# FG_Sce.net
KiCad netlist of a schematic drawn in Altium Designer
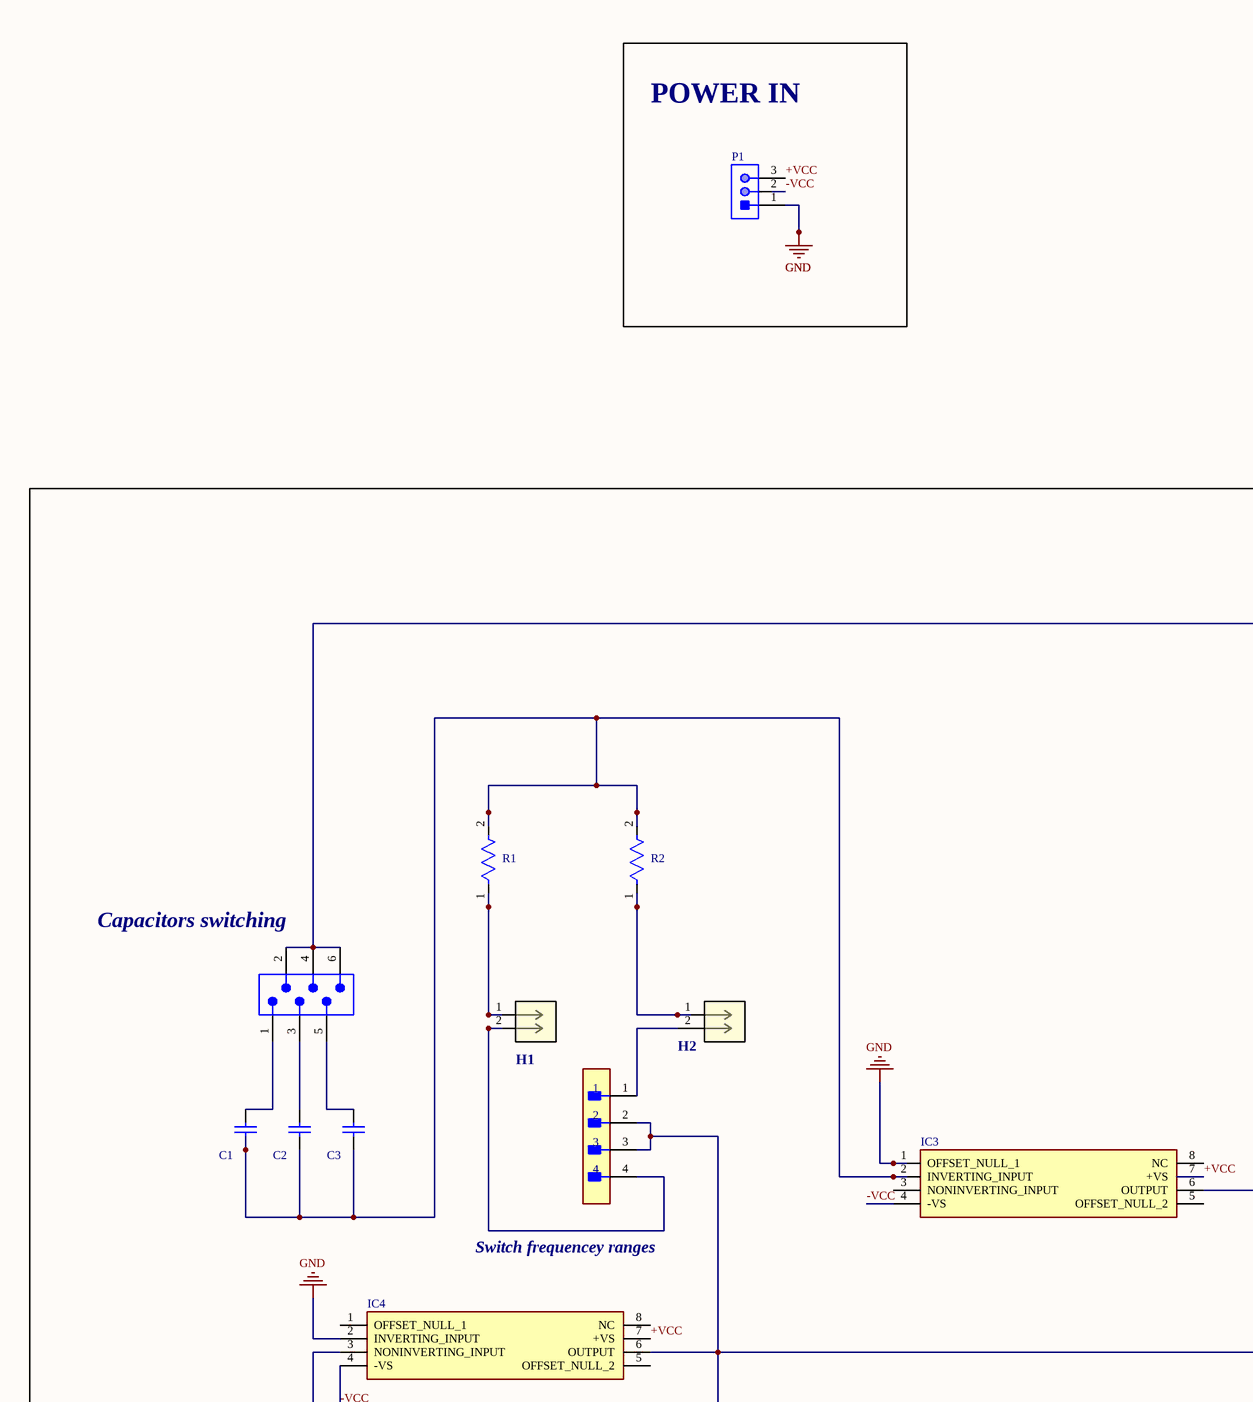
[diagram p0: FG Sce.SchDoc, top left]
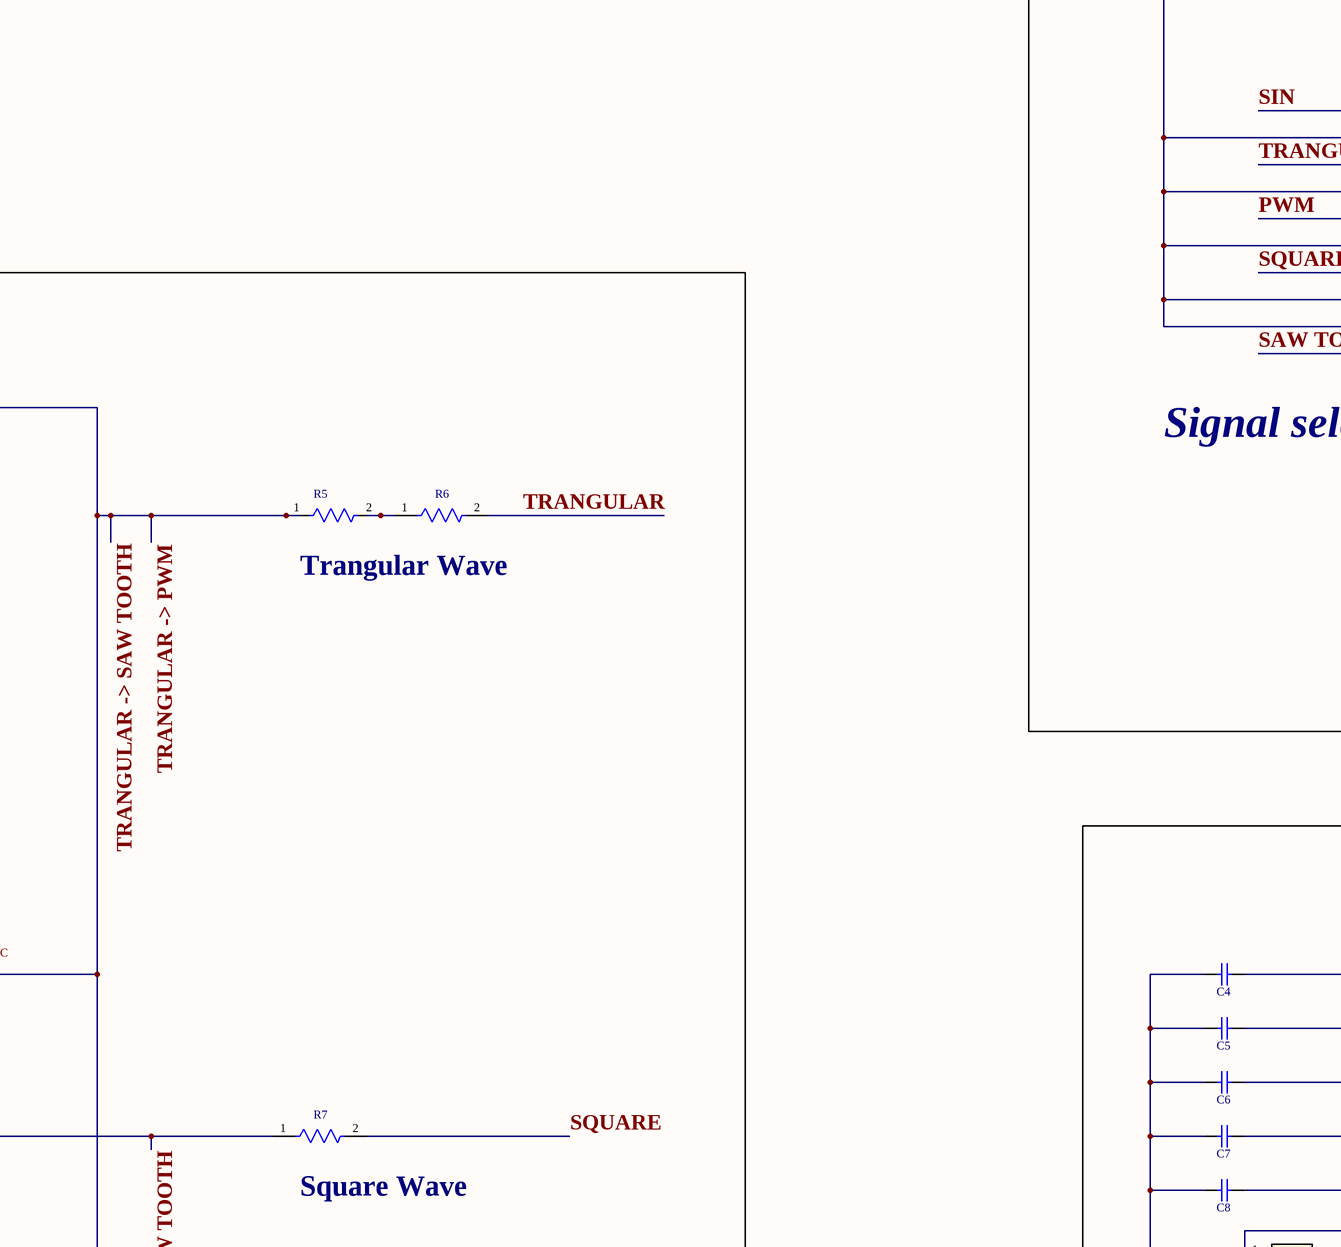
[diagram p1: FG Sce.SchDoc, top middle]
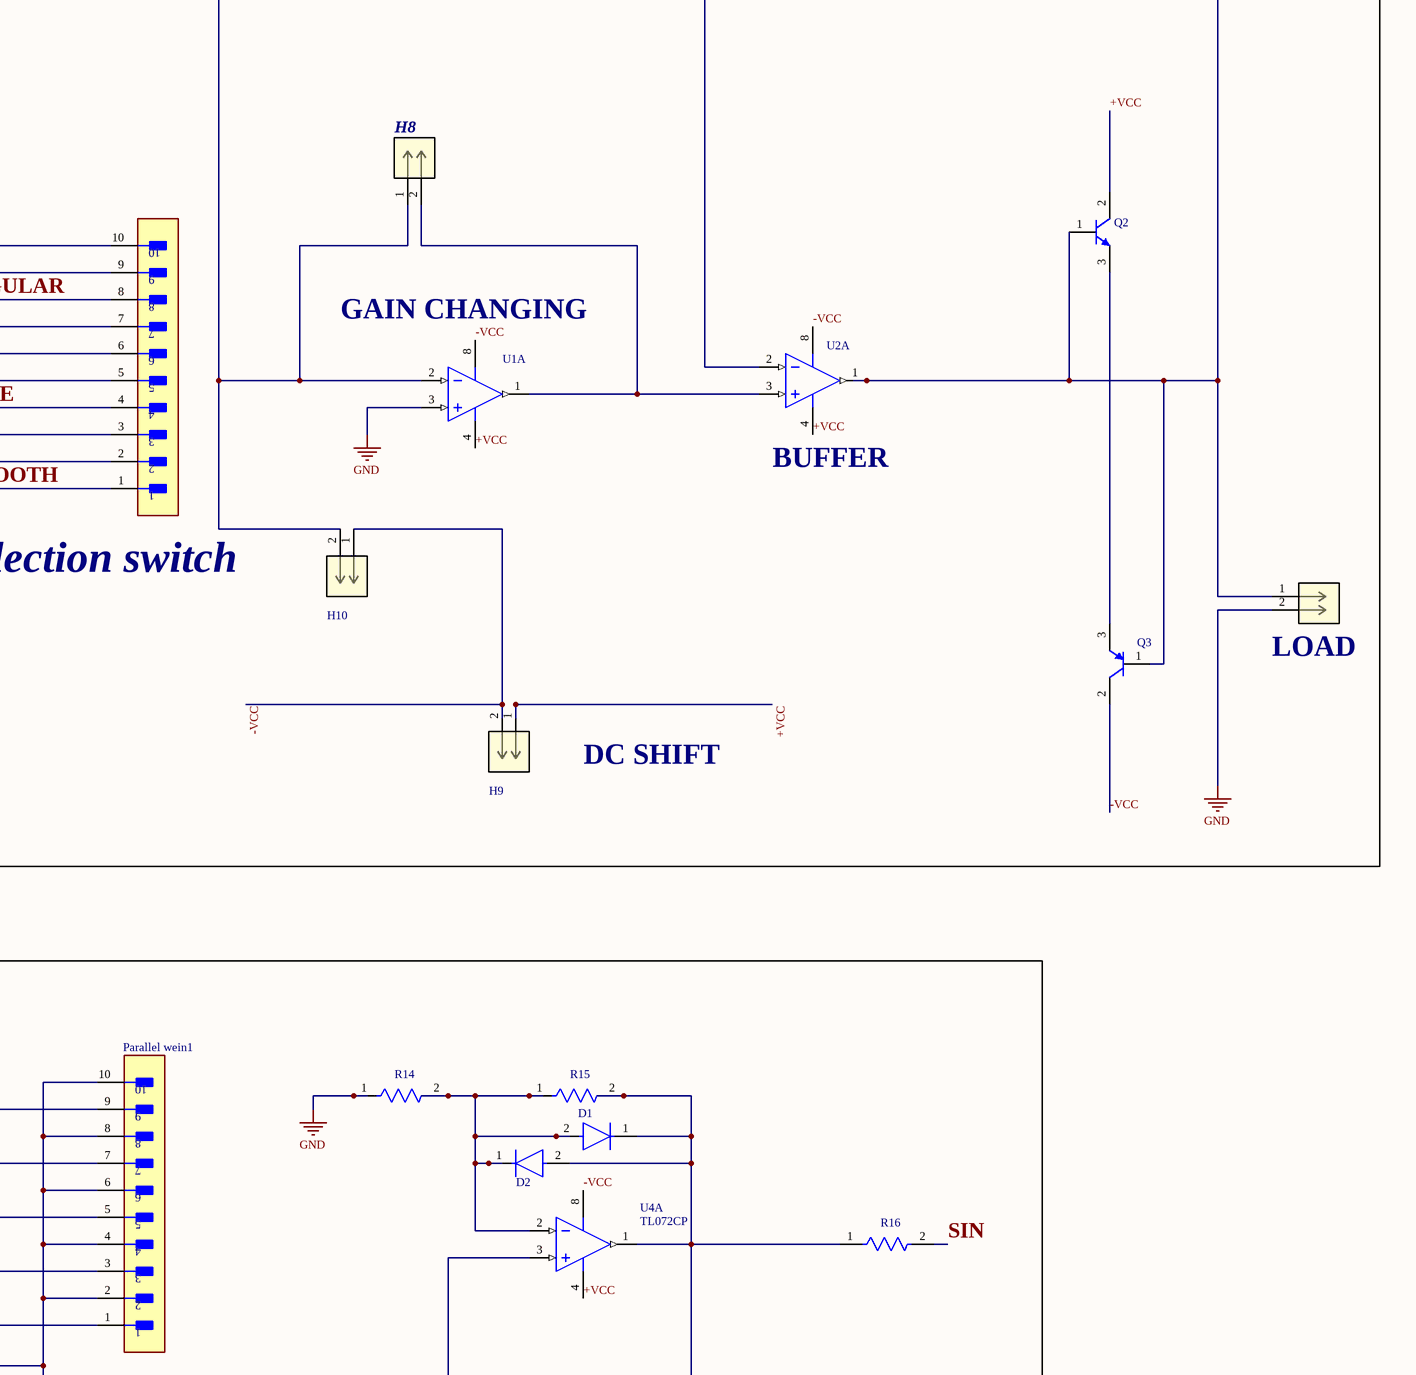
[diagram p2: FG Sce.SchDoc, top right]
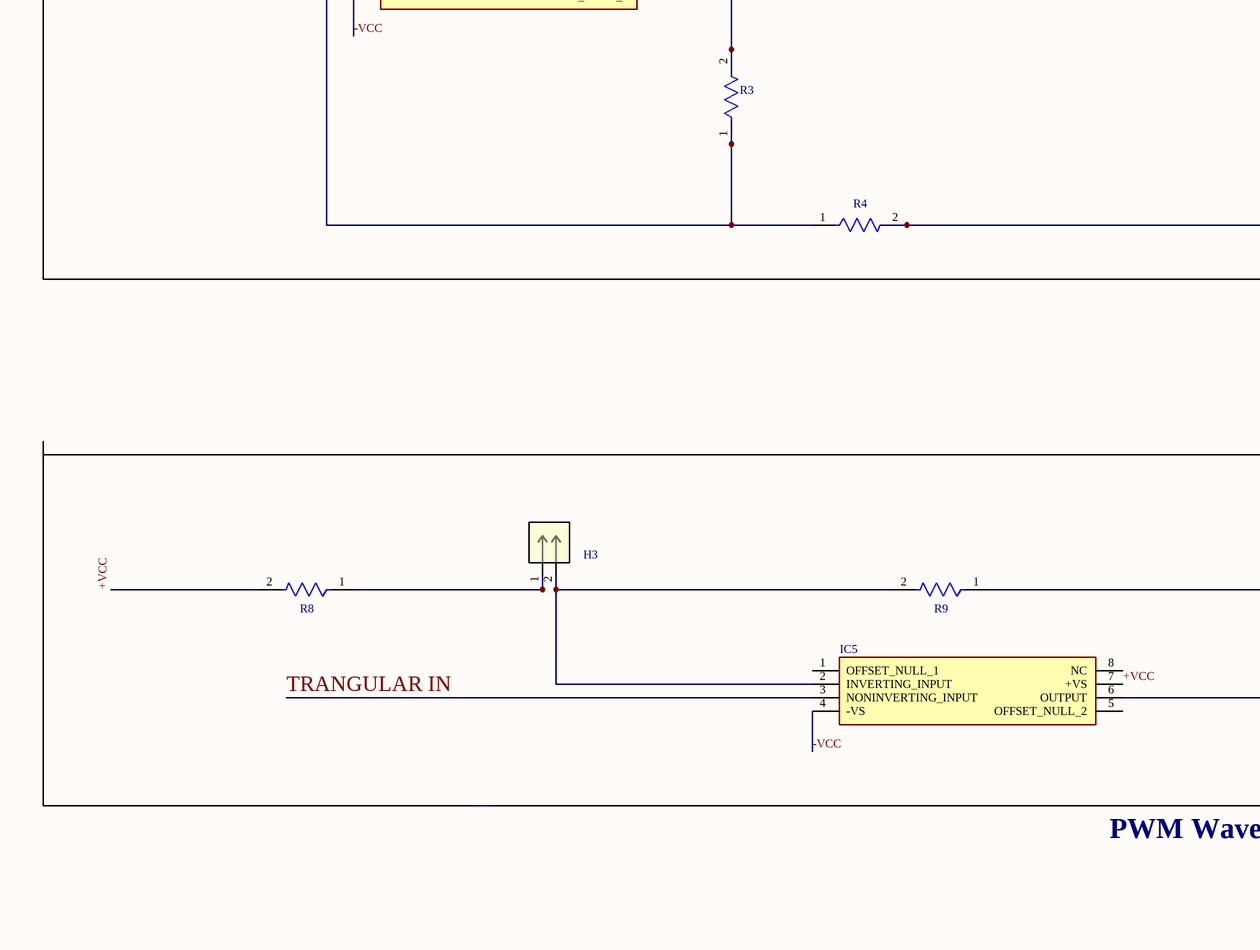
[diagram p3: FG Sce.SchDoc, bottom left]
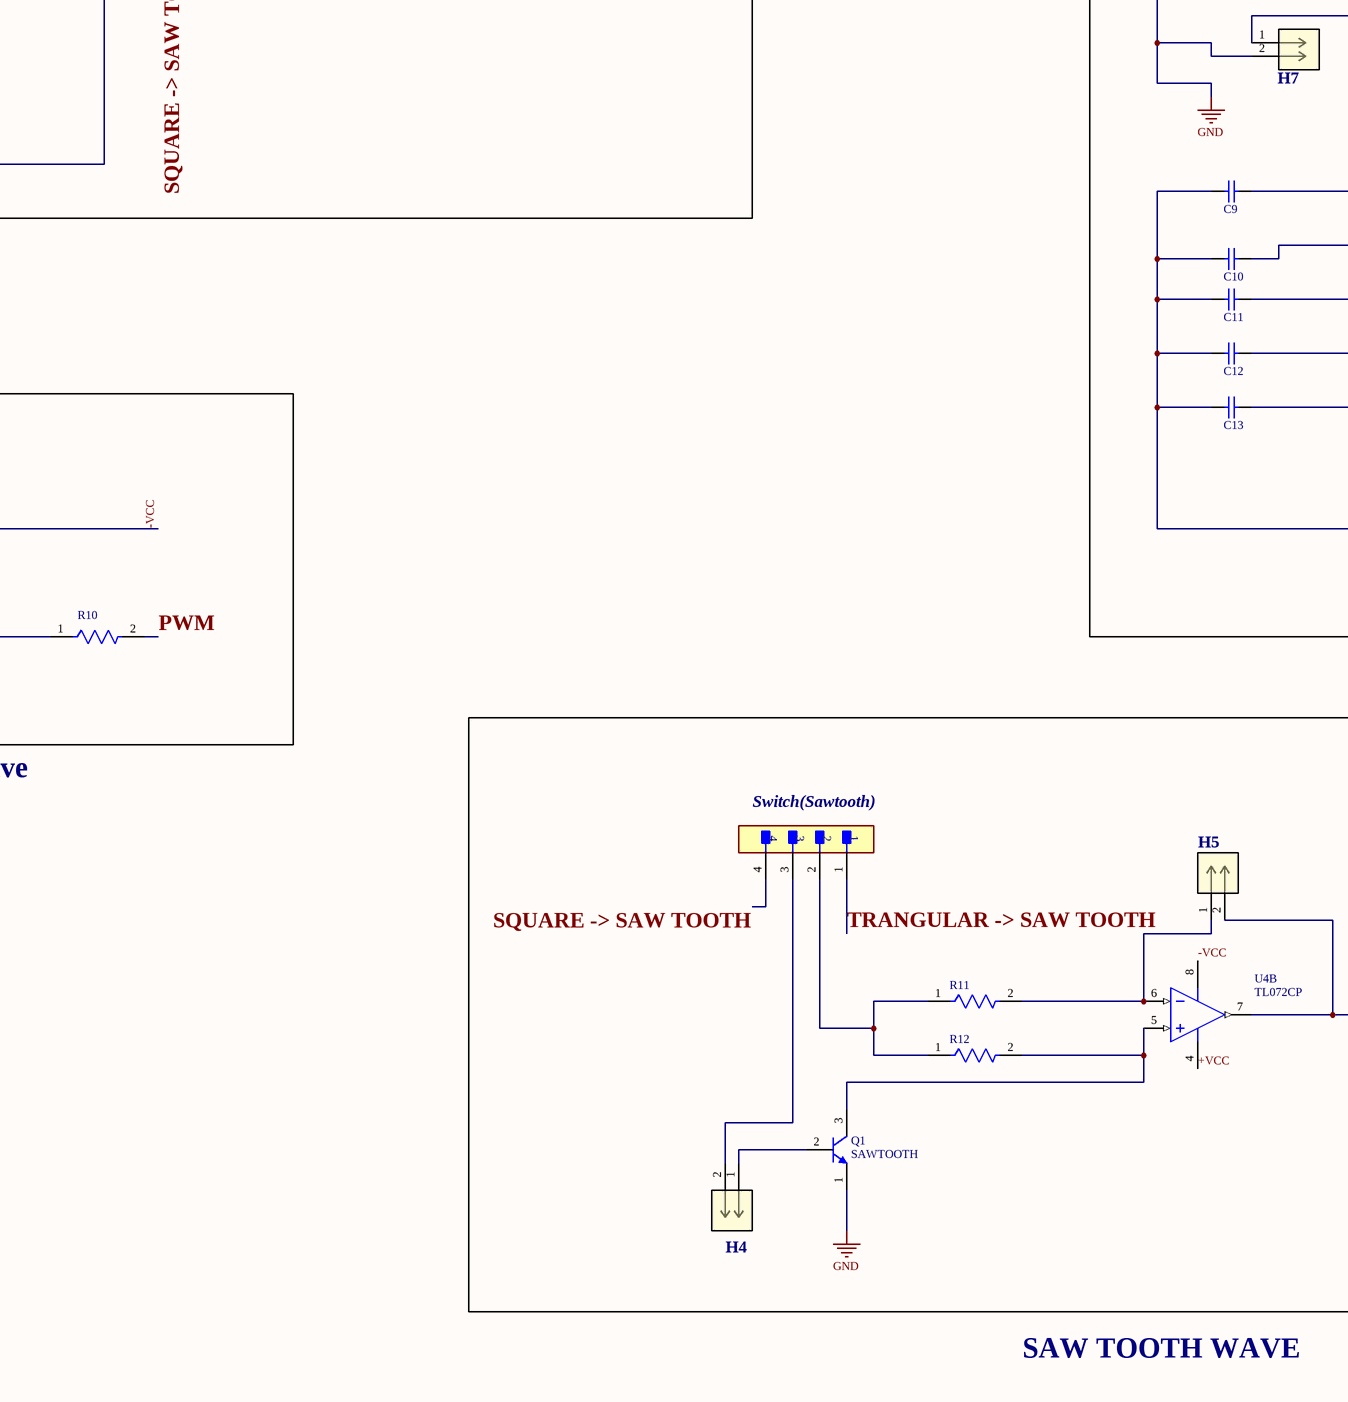
[diagram p4: FG Sce.SchDoc, bottom middle]
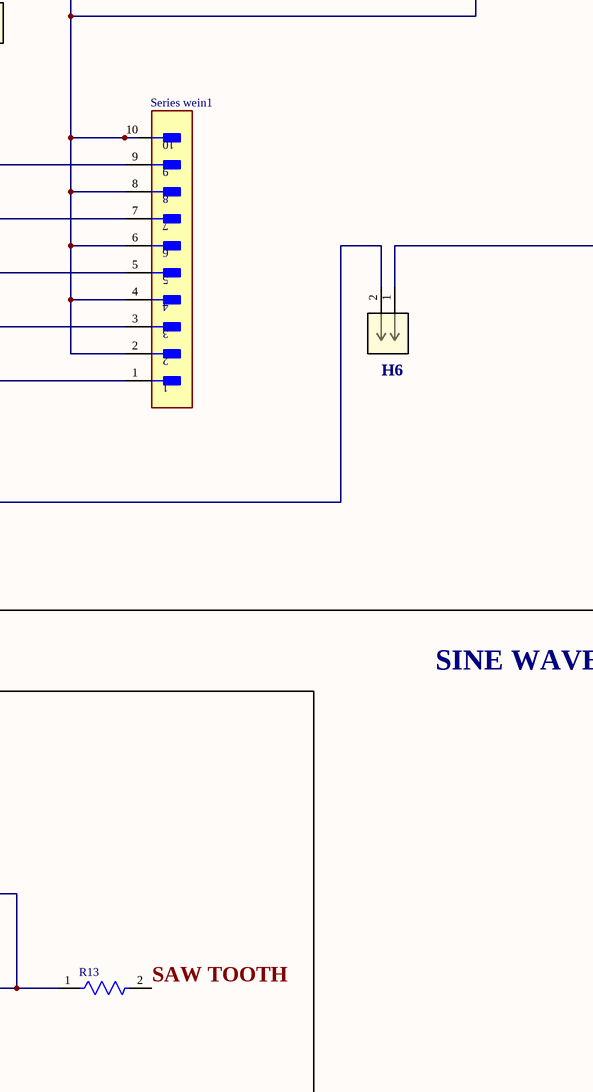
[diagram p5: FG Sce.SchDoc, bottom right]

(export (version "E")
  (design (tool "Eeschema 10.0.6"))
  (components
    (comp (ref "C1")
      (value "1uF")
      (footprint "KEMT-C333C105M5U5TA-2")
      (fields (field (name "MANUFACTURER") "Kemet") (field (name "TOLERANCE") "20%"))
      (libsource (lib "Altium Content Vault") (part "CAP-NP-2"))
    )
    (comp (ref "C2")
      (value "0.1uF")
      (footprint "KEMT-C333C105M5U5TA-2")
      (fields (field (name "MANUFACTURER") "Kemet") (field (name "TOLERANCE") "20%"))
      (libsource (lib "Altium Content Vault") (part "CAP-NP-2"))
    )
    (comp (ref "C3")
      (value "0.01uF")
      (footprint "KEMT-C333C105M5U5TA-2")
      (fields (field (name "MANUFACTURER") "Kemet") (field (name "TOLERANCE") "20%"))
      (libsource (lib "Altium Content Vault") (part "CAP-NP-2"))
    )
    (comp (ref "C4")
      (value "10uF")
      (footprint "KEMT-C333C105M5U5TA-2")
      (fields (field (name "MANUFACTURER") "Kemet") (field (name "TOLERANCE") "20%"))
      (libsource (lib "Altium Content Vault") (part "CAP-NP-2"))
    )
    (comp (ref "C5")
      (value "1uF")
      (footprint "KEMT-C333C105M5U5TA-2")
      (fields (field (name "MANUFACTURER") "Kemet") (field (name "TOLERANCE") "20%"))
      (libsource (lib "Altium Content Vault") (part "CAP-NP-2"))
    )
    (comp (ref "C6")
      (value "100nF")
      (footprint "KEMT-C333C105M5U5TA-2")
      (fields (field (name "MANUFACTURER") "Kemet") (field (name "TOLERANCE") "20%"))
      (libsource (lib "Altium Content Vault") (part "CAP-NP-2"))
    )
    (comp (ref "C7")
      (value "10nF")
      (footprint "KEMT-C333C105M5U5TA-2")
      (fields (field (name "MANUFACTURER") "Kemet") (field (name "TOLERANCE") "20%"))
      (libsource (lib "Altium Content Vault") (part "CAP-NP-2"))
    )
    (comp (ref "C8")
      (value "1nF")
      (footprint "KEMT-C333C105M5U5TA-2")
      (fields (field (name "MANUFACTURER") "Kemet") (field (name "TOLERANCE") "20%"))
      (libsource (lib "Altium Content Vault") (part "CAP-NP-2"))
    )
    (comp (ref "C9")
      (value "10uF")
      (footprint "KEMT-C333C105M5U5TA-2")
      (fields (field (name "MANUFACTURER") "Kemet") (field (name "TOLERANCE") "20%"))
      (libsource (lib "Altium Content Vault") (part "CAP-NP-2"))
    )
    (comp (ref "C10")
      (value "1uF")
      (footprint "KEMT-C333C105M5U5TA-2")
      (fields (field (name "MANUFACTURER") "Kemet") (field (name "TOLERANCE") "20%"))
      (libsource (lib "Altium Content Vault") (part "CAP-NP-2"))
    )
    (comp (ref "C11")
      (value "100nF")
      (footprint "KEMT-C333C105M5U5TA-2")
      (fields (field (name "MANUFACTURER") "Kemet") (field (name "TOLERANCE") "20%"))
      (libsource (lib "Altium Content Vault") (part "CAP-NP-2"))
    )
    (comp (ref "C12")
      (value "10nF")
      (footprint "KEMT-C333C105M5U5TA-2")
      (fields (field (name "MANUFACTURER") "Kemet") (field (name "TOLERANCE") "20%"))
      (libsource (lib "Altium Content Vault") (part "CAP-NP-2"))
    )
    (comp (ref "C13")
      (value "1nF")
      (footprint "KEMT-C333C105M5U5TA-2")
      (fields (field (name "MANUFACTURER") "Kemet") (field (name "TOLERANCE") "20%"))
      (libsource (lib "Altium Content Vault") (part "CAP-NP-2"))
    )
    (comp (ref "Capacitors switching")
      (value "690357100672")
      (footprint "690357100672")
      (libsource (lib "Altium Content Vault") (part "MM_Male_06P"))
    )
    (comp (ref "D1")
      (value "1N4148")
      (footprint "FP-017AG-MFG")
      (description "DIODE GEN PURP 100V 200MA DO35")
      (fields (field (name "VOLTAGE") "100V"))
      (libsource (lib "Altium Content Vault") (part "d7152d700b627762746794eb795d46e"))
    )
    (comp (ref "D2")
      (value "1N4148")
      (footprint "FP-017AG-MFG")
      (description "DIODE GEN PURP 100V 200MA DO35")
      (fields (field (name "VOLTAGE") "100V"))
      (libsource (lib "Altium Content Vault") (part "d7152d700b627762746794eb795d46e"))
    )
    (comp (ref "H1")
      (value "10KOHM POTENTIOMETER")
      (footprint "2Pins_AMP")
      (description "No Description Available")
      (libsource (lib "") (part "67997-402HLF_1"))
    )
    (comp (ref "H2")
      (value "200KOHM POTENTIOMETER")
      (footprint "2Pins_AMP")
      (description "No Description Available")
      (libsource (lib "") (part "67997-402HLF_1"))
    )
    (comp (ref "H3")
      (value "5Kohm Potentiometer")
      (footprint "2Pins_AMP")
      (description "No Description Available")
      (libsource (lib "67997-402HLF") (part "67997-402HLF"))
    )
    (comp (ref "H4")
      (value "100KOHM POTENTIOMETER")
      (footprint "2Pins_AMP")
      (description "No Description Available")
      (libsource (lib "") (part "67997-402HLF_2"))
    )
    (comp (ref "H5")
      (value "10Kohm potentiometer")
      (footprint "2Pins_AMP")
      (description "No Description Available")
      (libsource (lib "67997-402HLF") (part "67997-402HLF"))
    )
    (comp (ref "H6")
      (value "10Kohm potentiometer")
      (footprint "2Pins_AMP")
      (description "No Description Available")
      (libsource (lib "") (part "67997-402HLF_2"))
    )
    (comp (ref "H7")
      (value "10Kohm potentiometer")
      (footprint "2Pins_AMP")
      (description "No Description Available")
      (libsource (lib "") (part "67997-402HLF_1"))
    )
    (comp (ref "H8")
      (value "100kohm potentiometer")
      (footprint "2Pins_AMP")
      (description "No Description Available")
      (libsource (lib "67997-402HLF") (part "67997-402HLF"))
    )
    (comp (ref "H9")
      (value "10Kohm Potentiometer")
      (footprint "2Pins_AMP")
      (description "No Description Available")
      (libsource (lib "") (part "67997-402HLF_2"))
    )
    (comp (ref "H10")
      (value "10Kohm Potentiometer")
      (footprint "2Pins_AMP")
      (description "No Description Available")
      (libsource (lib "") (part "67997-402HLF_2"))
    )
    (comp (ref "IC3")
      (value "AD711JN")
      (footprint "SamacSys:DIP794W56P254L928H457Q8N")
      (description "Integrated Circuit")
      (libsource (lib "*") (part "AD711JN"))
    )
    (comp (ref "IC4")
      (value "AD711JN")
      (footprint "SamacSys:DIP794W56P254L928H457Q8N")
      (description "Integrated Circuit")
      (libsource (lib "*") (part "AD711JN"))
    )
    (comp (ref "IC5")
      (value "AD711JN")
      (footprint "SamacSys:DIP794W56P254L928H457Q8N")
      (description "Integrated Circuit")
      (libsource (lib "*") (part "AD711JN"))
    )
    (comp (ref "LOAD")
      (value "67997-402HLF")
      (footprint "2Pins_AMP")
      (description "No Description Available")
      (libsource (lib "") (part "67997-402HLF_1"))
    )
    (comp (ref "P1")
      (value "292161-3")
      (footprint "TECO-292161-3_V")
      (fields (field (name "MANUFACTURER") "TE Connectivity"))
      (libsource (lib "Altium Content Vault") (part "CN-1P-M-R3"))
    )
    (comp (ref "Parallel wein1")
      (value "in 1")
      (footprint "FP-4-644456-0-MFG")
      (description "CONN HEADER VERT 10POS 2.54MM")
      (fields
        (field (name "OCTOPART") "https://octopart.com/4-644456-0-te+connectivity-39514173")
        (field (name "MANUFACTURER PART NUMBER") "4-644456-0")
      )
      (libsource (lib "Altium Content Vault") (part "aee40dc8b284c03a16094555aa210be"))
    )
    (comp (ref "Q1")
      (value "SAWTOOTH")
      (footprint "FAIR-TO-92")
      (description "NPN General-Purpose Amplifier, 40 V VCEO, 0.2 A, -55 to 150 degC, 2-Pin TO-92, RoHS, Bulk")
      (fields (field (name "MANUFACTURER") "FairchildSemiconductor"))
      (libsource (lib "Altium Content Vault") (part "NPN-E1B2C3-3"))
    )
    (comp (ref "Q2")
      (value "TIP31A")
      (footprint "ONSC-TO-220-3-221A-09")
      (description "Complementary Silicon Plastic Power Transistor, 3-Pin TO-220, Tube")
      (fields (field (name "MANUFACTURER") "On Semiconductor"))
      (libsource (lib "Altium Content Vault") (part "ONSC-NPN-B1C2E3-3_C"))
    )
    (comp (ref "Q3")
      (value "TIP32A")
      (footprint "ONSC-TO-220-3-221A-09")
      (description "Complementary Silicon Plastic Power Transistor, 3-Pin TO-220, Tube")
      (fields (field (name "MANUFACTURER") "On Semiconductor"))
      (libsource (lib "Altium Content Vault") (part "ONSC-PNP-B1C2E3-3"))
    )
    (comp (ref "R1")
      (value "150ohm")
      (footprint "FP-RLR07-MFG")
      (description "RLR07C7501GSB14 Res Metal Film 7.5K Ohm 2% 1/4W ±100ppm/°C 0.001% Conformal AXL Thru-Hole Bulk")
      (fields (field (name "TOLERANCE") "2%"))
      (libsource (lib "Altium Content Vault") (part "1029c3af85768c4190bb7ad29bc67b5"))
    )
    (comp (ref "R2")
      (value "10K")
      (footprint "FP-RLR07-MFG")
      (description "RLR07C7501GSB14 Res Metal Film 7.5K Ohm 2% 1/4W ±100ppm/°C 0.001% Conformal AXL Thru-Hole Bulk")
      (fields (field (name "TOLERANCE") "2%"))
      (libsource (lib "Altium Content Vault") (part "1029c3af85768c4190bb7ad29bc67b5"))
    )
    (comp (ref "R3")
      (value "1K")
      (footprint "FP-MBB0207-MFG")
      (description "RES 10K OHM 0.6W 1% AXIAL")
      (fields (field (name "TOLERANCE") "1%"))
      (libsource (lib "Altium Content Vault") (part "1029c3af85768c4190bb7ad29bc67b5"))
    )
    (comp (ref "R4")
      (value "150OHM")
      (footprint "FP-MBB0207-MFG")
      (description "RES 10K OHM 0.6W 1% AXIAL")
      (fields (field (name "TOLERANCE") "1%"))
      (libsource (lib "Altium Content Vault") (part "1029c3af85768c4190bb7ad29bc67b5"))
    )
    (comp (ref "R5")
      (value "6.8K")
      (footprint "FP-MBB0207-MFG")
      (description "RES 10K OHM 0.6W 1% AXIAL")
      (fields (field (name "TOLERANCE") "1%"))
      (libsource (lib "Altium Content Vault") (part "1029c3af85768c4190bb7ad29bc67b5"))
    )
    (comp (ref "R6")
      (value "10K")
      (footprint "FP-MBB0207-MFG")
      (description "RES 10K OHM 0.6W 1% AXIAL")
      (fields (field (name "TOLERANCE") "1%"))
      (libsource (lib "Altium Content Vault") (part "1029c3af85768c4190bb7ad29bc67b5"))
    )
    (comp (ref "R7")
      (value "10K")
      (footprint "FP-MBB0207-MFG")
      (description "RES 10K OHM 0.6W 1% AXIAL")
      (fields (field (name "TOLERANCE") "1%"))
      (libsource (lib "Altium Content Vault") (part "1029c3af85768c4190bb7ad29bc67b5"))
    )
    (comp (ref "R8")
      (value "10K")
      (footprint "FP-MBB0207-MFG")
      (description "RES 10K OHM 0.6W 1% AXIAL")
      (fields (field (name "TOLERANCE") "1%"))
      (libsource (lib "Altium Content Vault") (part "1029c3af85768c4190bb7ad29bc67b5"))
    )
    (comp (ref "R9")
      (value "10K")
      (footprint "FP-MBB0207-MFG")
      (description "RES 10K OHM 0.6W 1% AXIAL")
      (fields (field (name "TOLERANCE") "1%"))
      (libsource (lib "Altium Content Vault") (part "1029c3af85768c4190bb7ad29bc67b5"))
    )
    (comp (ref "R10")
      (value "68Kohm")
      (footprint "FP-MBB0207-MFG")
      (description "RES 10K OHM 0.6W 1% AXIAL")
      (fields (field (name "TOLERANCE") "1%"))
      (libsource (lib "Altium Content Vault") (part "1029c3af85768c4190bb7ad29bc67b5"))
    )
    (comp (ref "R11")
      (value "10K")
      (footprint "FP-MBB0207-MFG")
      (description "RES 10K OHM 0.6W 1% AXIAL")
      (fields (field (name "TOLERANCE") "1%"))
      (libsource (lib "Altium Content Vault") (part "1029c3af85768c4190bb7ad29bc67b5"))
    )
    (comp (ref "R12")
      (value "10K")
      (footprint "FP-MBB0207-MFG")
      (description "RES 10K OHM 0.6W 1% AXIAL")
      (fields (field (name "TOLERANCE") "1%"))
      (libsource (lib "Altium Content Vault") (part "1029c3af85768c4190bb7ad29bc67b5"))
    )
    (comp (ref "R13")
      (value "10k")
      (footprint "FP-MBB0207-MFG")
      (description "RES 10K OHM 0.6W 1% AXIAL")
      (fields (field (name "TOLERANCE") "1%"))
      (libsource (lib "Altium Content Vault") (part "1029c3af85768c4190bb7ad29bc67b5"))
    )
    (comp (ref "R14")
      (value "5K")
      (footprint "FP-MBB0207-MFG")
      (description "RES 10K OHM 0.6W 1% AXIAL")
      (fields (field (name "TOLERANCE") "1%"))
      (libsource (lib "Altium Content Vault") (part "1029c3af85768c4190bb7ad29bc67b5"))
    )
    (comp (ref "R15")
      (value "10K")
      (footprint "FP-MBB0207-MFG")
      (description "RES 10K OHM 0.6W 1% AXIAL")
      (fields (field (name "TOLERANCE") "1%"))
      (libsource (lib "Altium Content Vault") (part "1029c3af85768c4190bb7ad29bc67b5"))
    )
    (comp (ref "R16")
      (value "0.5K")
      (footprint "FP-MBB0207-MFG")
      (description "RES 10K OHM 0.6W 1% AXIAL")
      (fields (field (name "TOLERANCE") "1%"))
      (libsource (lib "Altium Content Vault") (part "1029c3af85768c4190bb7ad29bc67b5"))
    )
    (comp (ref "Series wein1")
      (value "in2")
      (footprint "FP-4-644456-0-MFG")
      (description "CONN HEADER VERT 10POS 2.54MM")
      (fields
        (field (name "OCTOPART") "https://octopart.com/4-644456-0-te+connectivity-39514173")
        (field (name "MANUFACTURER PART NUMBER") "4-644456-0")
      )
      (libsource (lib "Altium Content Vault") (part "aee40dc8b284c03a16094555aa210be"))
    )
    (comp (ref "Signal selection switch")
      (value "4-644456-0")
      (footprint "FP-4-644456-0-MFG")
      (description "CONN HEADER VERT 10POS 2.54MM")
      (fields
        (field (name "OCTOPART") "https://octopart.com/4-644456-0-te+connectivity-39514173")
        (field (name "MANUFACTURER") "TE Connectivity")
      )
      (libsource (lib "Altium Content Vault") (part "aee40dc8b284c03a16094555aa210be"))
    )
    (comp (ref "Switch frequencey ranges")
      (value "FREQ")
      (footprint "FP-HTSW-102-07-G-D-MFG")
      (description "CONN HEADER VERT 4POS 2.54MM")
      (fields
        (field (name "MANUFACTURER") "Samtec")
        (field (name "MANUFACTURER PART NUMBER") "HTSW-102-07-G-D")
      )
      (libsource (lib "Altium Content Vault") (part "299a8cea1bdcbc3624fe62c390fa72c"))
    )
    (comp (ref "Switch(Sawtooth)")
      (value "HTSW-102-07-G-D")
      (footprint "FP-HTSW-102-07-G-D-MFG")
      (description "CONN HEADER VERT 4POS 2.54MM")
      (fields
        (field (name "MANUFACTURER") "Samtec")
        (field (name "OCTOPART") "https://octopart.com/htsw-102-07-g-d-samtec-10531767")
      )
      (libsource (lib "") (part "299a8cea1bdcbc3624fe62c390fa72c_1"))
    )
    (comp (ref "U1")
      (value "TL072CP")
      (footprint "P0008A")
      (fields (field (name "MANUFACTURER") "Texas Instruments"))
      (libsource (lib "Altium Content Vault") (part "TI-AMP-D6-2-8_D"))
    )
    (comp (ref "U2")
      (value "TL072CP")
      (footprint "P0008A")
      (fields (field (name "MANUFACTURER") "Texas Instruments"))
      (libsource (lib "Altium Content Vault") (part "TI-AMP-D6-2-8_D"))
    )
    (comp (ref "U4")
      (value "TL072CP")
      (footprint "P0008A")
      (fields (field (name "MANUFACTURER") "Texas Instruments"))
      (libsource (lib "Altium Content Vault") (part "TI-AMP-D6-2-8_D"))
    )
  )
  (nets
    (net (code "1") (name "/+VCC") (class "Default")
      (node (ref "H9") (pin "1") (pinfunction "1_1") (pintype "passive"))
      (node (ref "IC3") (pin "7") (pinfunction "+VS_7") (pintype "passive"))
      (node (ref "IC4") (pin "7") (pinfunction "+VS_7") (pintype "passive"))
      (node (ref "IC5") (pin "7") (pinfunction "+VS_7") (pintype "passive"))
      (node (ref "P1") (pin "3") (pinfunction "3_3") (pintype "passive"))
      (node (ref "Q2") (pin "2") (pinfunction "C_2") (pintype "passive"))
      (node (ref "R8") (pin "2") (pinfunction "2_2") (pintype "passive"))
      (node (ref "U1") (pin "4") (pinfunction "VCC-_4") (pintype "power_in"))
      (node (ref "U2") (pin "4") (pinfunction "VCC-_4") (pintype "power_in"))
      (node (ref "U4") (pin "4") (pinfunction "VCC-_4") (pintype "power_in"))
    )
    (net (code "2") (name "/-VCC") (class "Default")
      (node (ref "H10") (pin "1") (pinfunction "1_1") (pintype "passive"))
      (node (ref "H9") (pin "2") (pinfunction "2_2") (pintype "passive"))
      (node (ref "IC3") (pin "4") (pinfunction "-VS_4") (pintype "passive"))
      (node (ref "IC4") (pin "4") (pinfunction "-VS_4") (pintype "passive"))
      (node (ref "IC5") (pin "4") (pinfunction "-VS_4") (pintype "passive"))
      (node (ref "P1") (pin "2") (pinfunction "2_2") (pintype "passive"))
      (node (ref "Q3") (pin "2") (pinfunction "C_2") (pintype "passive"))
      (node (ref "R9") (pin "1") (pinfunction "1_1") (pintype "passive"))
      (node (ref "U1") (pin "8") (pinfunction "VCC+_8") (pintype "power_in"))
      (node (ref "U2") (pin "8") (pinfunction "VCC+_8") (pintype "power_in"))
      (node (ref "U4") (pin "8") (pinfunction "VCC+_8") (pintype "power_in"))
    )
    (net (code "3") (name "/PWM") (class "Default")
      (node (ref "R10") (pin "2") (pinfunction "2_2") (pintype "passive"))
      (node (ref "Signal selection switch") (pin "6") (pinfunction "6_6") (pintype "passive"))
    )
    (net (code "4") (name "/SAW TOOTH") (class "Default")
      (node (ref "R13") (pin "2") (pinfunction "2_2") (pintype "passive"))
      (node (ref "Signal selection switch") (pin "1") (pinfunction "1_1") (pintype "passive"))
    )
    (net (code "5") (name "/SIN") (class "Default")
      (node (ref "R16") (pin "2") (pinfunction "2_2") (pintype "passive"))
      (node (ref "Signal selection switch") (pin "10") (pinfunction "10_10") (pintype "passive"))
    )
    (net (code "6") (name "/SQUARE") (class "Default")
      (node (ref "R7") (pin "2") (pinfunction "2_2") (pintype "passive"))
      (node (ref "Signal selection switch") (pin "4") (pinfunction "4_4") (pintype "passive"))
    )
    (net (code "7") (name "/SQUARE -> SAW TOOTH") (class "Default")
      (node (ref "IC4") (pin "6") (pinfunction "OUTPUT_6") (pintype "passive"))
      (node (ref "R3") (pin "2") (pinfunction "2_2") (pintype "passive"))
      (node (ref "R7") (pin "1") (pinfunction "1_1") (pintype "passive"))
      (node (ref "Switch frequencey ranges") (pin "2") (pinfunction "2_2") (pintype "passive"))
      (node (ref "Switch frequencey ranges") (pin "3") (pinfunction "3_3") (pintype "passive"))
      (node (ref "Switch(Sawtooth)") (pin "4") (pinfunction "4_4") (pintype "passive"))
    )
    (net (code "8") (name "/TRANGULAR") (class "Default")
      (node (ref "R6") (pin "2") (pinfunction "2_2") (pintype "passive"))
      (node (ref "Signal selection switch") (pin "8") (pinfunction "8_8") (pintype "passive"))
    )
    (net (code "9") (name "/TRANGULAR -> PWM") (class "Default")
      (node (ref "Capacitors switching") (pin "2") (pinfunction "2_2") (pintype "passive"))
      (node (ref "Capacitors switching") (pin "4") (pinfunction "4_4") (pintype "passive"))
      (node (ref "Capacitors switching") (pin "6") (pinfunction "6_6") (pintype "passive"))
      (node (ref "IC3") (pin "6") (pinfunction "OUTPUT_6") (pintype "passive"))
      (node (ref "R4") (pin "2") (pinfunction "2_2") (pintype "passive"))
      (node (ref "R5") (pin "1") (pinfunction "1_1") (pintype "passive"))
      (node (ref "Switch(Sawtooth)") (pin "1") (pinfunction "1_1") (pintype "passive"))
    )
    (net (code "10") (name "/TRANGULAR IN") (class "Default")
      (node (ref "IC5") (pin "3") (pinfunction "NONINVERTING_INPUT_3") (pintype "passive"))
    )
    (net (code "11") (name "GND") (class "Default")
      (node (ref "C4") (pin "2") (pinfunction "2_2") (pintype "passive"))
      (node (ref "C5") (pin "2") (pinfunction "2_2") (pintype "passive"))
      (node (ref "C6") (pin "2") (pinfunction "2_2") (pintype "passive"))
      (node (ref "C7") (pin "2") (pinfunction "2_2") (pintype "passive"))
      (node (ref "C8") (pin "2") (pinfunction "2_2") (pintype "passive"))
      (node (ref "H7") (pin "2") (pinfunction "2_2") (pintype "passive"))
      (node (ref "IC3") (pin "1") (pinfunction "OFFSET_NULL_1_1") (pintype "passive"))
      (node (ref "IC4") (pin "2") (pinfunction "INVERTING_INPUT_2") (pintype "passive"))
      (node (ref "LOAD") (pin "2") (pinfunction "2_2") (pintype "passive"))
      (node (ref "P1") (pin "1") (pinfunction "1_1") (pintype "passive"))
      (node (ref "Q1") (pin "1") (pinfunction "E_1") (pintype "passive"))
      (node (ref "R14") (pin "1") (pinfunction "1_1") (pintype "passive"))
      (node (ref "U1") (pin "3") (pinfunction "IN1+_3") (pintype "input"))
    )
    (net (code "12") (name "Net-(C1-Pad2)") (class "Default")
      (node (ref "C1") (pin "2") (pinfunction "2_2") (pintype "passive"))
      (node (ref "Capacitors switching") (pin "1") (pinfunction "1_1") (pintype "passive"))
    )
    (net (code "13") (name "Net-(C2-Pad2)") (class "Default")
      (node (ref "C2") (pin "2") (pinfunction "2_2") (pintype "passive"))
      (node (ref "Capacitors switching") (pin "3") (pinfunction "3_3") (pintype "passive"))
    )
    (net (code "14") (name "Net-(C3-Pad2)") (class "Default")
      (node (ref "C3") (pin "2") (pinfunction "2_2") (pintype "passive"))
      (node (ref "Capacitors switching") (pin "5") (pinfunction "5_5") (pintype "passive"))
    )
    (net (code "15") (name "Net-(C4-Pad1)") (class "Default")
      (node (ref "C4") (pin "1") (pinfunction "1_1") (pintype "passive"))
      (node (ref "Parallel wein1") (pin "9") (pinfunction "9_9") (pintype "passive"))
    )
    (net (code "16") (name "Net-(C5-Pad1)") (class "Default")
      (node (ref "C5") (pin "1") (pinfunction "1_1") (pintype "passive"))
      (node (ref "Parallel wein1") (pin "7") (pinfunction "7_7") (pintype "passive"))
    )
    (net (code "17") (name "Net-(C6-Pad1)") (class "Default")
      (node (ref "C6") (pin "1") (pinfunction "1_1") (pintype "passive"))
      (node (ref "Parallel wein1") (pin "5") (pinfunction "5_5") (pintype "passive"))
    )
    (net (code "18") (name "Net-(C7-Pad1)") (class "Default")
      (node (ref "C7") (pin "1") (pinfunction "1_1") (pintype "passive"))
      (node (ref "Parallel wein1") (pin "3") (pinfunction "3_3") (pintype "passive"))
    )
    (net (code "19") (name "Net-(C8-Pad1)") (class "Default")
      (node (ref "C8") (pin "1") (pinfunction "1_1") (pintype "passive"))
      (node (ref "Parallel wein1") (pin "1") (pinfunction "1_1") (pintype "passive"))
    )
    (net (code "20") (name "Net-(C9-Pad1)") (class "Default")
      (node (ref "C9") (pin "1") (pinfunction "1_1") (pintype "passive"))
      (node (ref "Series wein1") (pin "9") (pinfunction "9_9") (pintype "passive"))
    )
    (net (code "21") (name "Net-(C10-Pad1)") (class "Default")
      (node (ref "C10") (pin "1") (pinfunction "1_1") (pintype "passive"))
      (node (ref "Series wein1") (pin "7") (pinfunction "7_7") (pintype "passive"))
    )
    (net (code "22") (name "Net-(C10-Pad2)") (class "Default")
      (node (ref "C10") (pin "2") (pinfunction "2_2") (pintype "passive"))
      (node (ref "C11") (pin "2") (pinfunction "2_2") (pintype "passive"))
      (node (ref "C12") (pin "2") (pinfunction "2_2") (pintype "passive"))
      (node (ref "C13") (pin "2") (pinfunction "2_2") (pintype "passive"))
      (node (ref "C9") (pin "2") (pinfunction "2_2") (pintype "passive"))
      (node (ref "H6") (pin "2") (pinfunction "2_2") (pintype "passive"))
    )
    (net (code "23") (name "Net-(C11-Pad1)") (class "Default")
      (node (ref "C11") (pin "1") (pinfunction "1_1") (pintype "passive"))
      (node (ref "Series wein1") (pin "5") (pinfunction "5_5") (pintype "passive"))
    )
    (net (code "24") (name "Net-(C12-Pad1)") (class "Default")
      (node (ref "C12") (pin "1") (pinfunction "1_1") (pintype "passive"))
      (node (ref "Series wein1") (pin "3") (pinfunction "3_3") (pintype "passive"))
    )
    (net (code "25") (name "Net-(C13-Pad1)") (class "Default")
      (node (ref "C13") (pin "1") (pinfunction "1_1") (pintype "passive"))
      (node (ref "Series wein1") (pin "1") (pinfunction "1_1") (pintype "passive"))
    )
    (net (code "26") (name "Net-(D1-A)") (class "Default")
      (node (ref "D1") (pin "2") (pinfunction "A_2") (pintype "passive"))
      (node (ref "D2") (pin "1") (pinfunction "C_1") (pintype "passive"))
      (node (ref "R14") (pin "2") (pinfunction "2_2") (pintype "passive"))
      (node (ref "R15") (pin "1") (pinfunction "1_1") (pintype "passive"))
      (node (ref "U4") (pin "2") (pinfunction "IN1-_2") (pintype "input"))
    )
    (net (code "27") (name "Net-(D1-C)") (class "Default")
      (node (ref "D1") (pin "1") (pinfunction "C_1") (pintype "passive"))
      (node (ref "D2") (pin "2") (pinfunction "A_2") (pintype "passive"))
      (node (ref "H6") (pin "1") (pinfunction "1_1") (pintype "passive"))
      (node (ref "R15") (pin "2") (pinfunction "2_2") (pintype "passive"))
      (node (ref "R16") (pin "1") (pinfunction "1_1") (pintype "passive"))
      (node (ref "U4") (pin "1") (pinfunction "OUT1_1") (pintype "output"))
    )
    (net (code "28") (name "Net-(H1-Pad1)") (class "Default")
      (node (ref "H1") (pin "1") (pinfunction "1_1") (pintype "passive"))
      (node (ref "R1") (pin "1") (pinfunction "1_1") (pintype "passive"))
    )
    (net (code "29") (name "Net-(H1-Pad2)") (class "Default")
      (node (ref "H1") (pin "2") (pinfunction "2_2") (pintype "passive"))
      (node (ref "Switch frequencey ranges") (pin "4") (pinfunction "4_4") (pintype "passive"))
    )
    (net (code "30") (name "Net-(H2-Pad1)") (class "Default")
      (node (ref "H2") (pin "1") (pinfunction "1_1") (pintype "passive"))
      (node (ref "R2") (pin "1") (pinfunction "1_1") (pintype "passive"))
    )
    (net (code "31") (name "Net-(H2-Pad2)") (class "Default")
      (node (ref "H2") (pin "2") (pinfunction "2_2") (pintype "passive"))
      (node (ref "Switch frequencey ranges") (pin "1") (pinfunction "1_1") (pintype "passive"))
    )
    (net (code "32") (name "Net-(H3-Pad1)") (class "Default")
      (node (ref "H3") (pin "1") (pinfunction "1_1") (pintype "passive"))
      (node (ref "R8") (pin "1") (pinfunction "1_1") (pintype "passive"))
    )
    (net (code "33") (name "Net-(H4-Pad2)") (class "Default")
      (node (ref "H4") (pin "2") (pinfunction "2_2") (pintype "passive"))
      (node (ref "Switch(Sawtooth)") (pin "3") (pinfunction "3_3") (pintype "passive"))
    )
    (net (code "34") (name "Net-(IC3-INVERTING_INPUT)") (class "Default")
      (node (ref "C1") (pin "1") (pinfunction "1_1") (pintype "passive"))
      (node (ref "C2") (pin "1") (pinfunction "1_1") (pintype "passive"))
      (node (ref "C3") (pin "1") (pinfunction "1_1") (pintype "passive"))
      (node (ref "IC3") (pin "2") (pinfunction "INVERTING_INPUT_2") (pintype "passive"))
      (node (ref "R1") (pin "2") (pinfunction "2_2") (pintype "passive"))
      (node (ref "R2") (pin "2") (pinfunction "2_2") (pintype "passive"))
    )
    (net (code "35") (name "Net-(IC4-NONINVERTING_INPUT)") (class "Default")
      (node (ref "IC4") (pin "3") (pinfunction "NONINVERTING_INPUT_3") (pintype "passive"))
      (node (ref "R3") (pin "1") (pinfunction "1_1") (pintype "passive"))
      (node (ref "R4") (pin "1") (pinfunction "1_1") (pintype "passive"))
    )
    (net (code "36") (name "Net-(IC5-INVERTING_INPUT)") (class "Default")
      (node (ref "H3") (pin "2") (pinfunction "2_2") (pintype "passive"))
      (node (ref "IC5") (pin "2") (pinfunction "INVERTING_INPUT_2") (pintype "passive"))
      (node (ref "R9") (pin "2") (pinfunction "2_2") (pintype "passive"))
    )
    (net (code "37") (name "Net-(IC5-OUTPUT)") (class "Default")
      (node (ref "IC5") (pin "6") (pinfunction "OUTPUT_6") (pintype "passive"))
      (node (ref "R10") (pin "1") (pinfunction "1_1") (pintype "passive"))
    )
    (net (code "38") (name "Net-(Q1-B)") (class "Default")
      (node (ref "H4") (pin "1") (pinfunction "1_1") (pintype "passive"))
      (node (ref "Q1") (pin "2") (pinfunction "B_2") (pintype "passive"))
    )
    (net (code "39") (name "Net-(Q1-C)") (class "Default")
      (node (ref "Q1") (pin "3") (pinfunction "C_3") (pintype "passive"))
      (node (ref "R12") (pin "2") (pinfunction "2_2") (pintype "passive"))
      (node (ref "U4") (pin "5") (pinfunction "IN2+_5") (pintype "input"))
    )
    (net (code "40") (name "Net-(Q2-B)") (class "Default")
      (node (ref "LOAD") (pin "1") (pinfunction "1_1") (pintype "passive"))
      (node (ref "Q2") (pin "1") (pinfunction "B_1") (pintype "passive"))
      (node (ref "Q3") (pin "1") (pinfunction "B_1") (pintype "passive"))
      (node (ref "U2") (pin "1") (pinfunction "OUT1_1") (pintype "output"))
      (node (ref "U2") (pin "2") (pinfunction "IN1-_2") (pintype "input"))
    )
    (net (code "41") (name "Net-(Q2-E)") (class "Default")
      (node (ref "Q2") (pin "3") (pinfunction "E_3") (pintype "passive"))
      (node (ref "Q3") (pin "3") (pinfunction "E_3") (pintype "passive"))
    )
    (net (code "42") (name "Net-(R5-Pad2)") (class "Default")
      (node (ref "R5") (pin "2") (pinfunction "2_2") (pintype "passive"))
      (node (ref "R6") (pin "1") (pinfunction "1_1") (pintype "passive"))
    )
    (net (code "43") (name "Net-(R11-Pad1)") (class "Default")
      (node (ref "R11") (pin "1") (pinfunction "1_1") (pintype "passive"))
      (node (ref "R12") (pin "1") (pinfunction "1_1") (pintype "passive"))
      (node (ref "Switch(Sawtooth)") (pin "2") (pinfunction "2_2") (pintype "passive"))
    )
    (net (code "44") (name "Net-(U1A-IN1-)") (class "Default")
      (node (ref "H10") (pin "2") (pinfunction "2_2") (pintype "passive"))
      (node (ref "H8") (pin "1") (pinfunction "1_1") (pintype "passive"))
      (node (ref "Signal selection switch") (pin "2") (pinfunction "2_2") (pintype "passive"))
      (node (ref "Signal selection switch") (pin "3") (pinfunction "3_3") (pintype "passive"))
      (node (ref "Signal selection switch") (pin "5") (pinfunction "5_5") (pintype "passive"))
      (node (ref "Signal selection switch") (pin "7") (pinfunction "7_7") (pintype "passive"))
      (node (ref "Signal selection switch") (pin "9") (pinfunction "9_9") (pintype "passive"))
      (node (ref "U1") (pin "2") (pinfunction "IN1-_2") (pintype "input"))
    )
    (net (code "45") (name "Net-(U1A-OUT1)") (class "Default")
      (node (ref "H8") (pin "2") (pinfunction "2_2") (pintype "passive"))
      (node (ref "U1") (pin "1") (pinfunction "OUT1_1") (pintype "output"))
      (node (ref "U2") (pin "3") (pinfunction "IN1+_3") (pintype "input"))
    )
    (net (code "46") (name "Net-(U4A-IN1+)") (class "Default")
      (node (ref "H7") (pin "1") (pinfunction "1_1") (pintype "passive"))
      (node (ref "Parallel wein1") (pin "10") (pinfunction "10_10") (pintype "passive"))
      (node (ref "Parallel wein1") (pin "2") (pinfunction "2_2") (pintype "passive"))
      (node (ref "Parallel wein1") (pin "4") (pinfunction "4_4") (pintype "passive"))
      (node (ref "Parallel wein1") (pin "6") (pinfunction "6_6") (pintype "passive"))
      (node (ref "Parallel wein1") (pin "8") (pinfunction "8_8") (pintype "passive"))
      (node (ref "Series wein1") (pin "10") (pinfunction "10_10") (pintype "passive"))
      (node (ref "Series wein1") (pin "2") (pinfunction "2_2") (pintype "passive"))
      (node (ref "Series wein1") (pin "4") (pinfunction "4_4") (pintype "passive"))
      (node (ref "Series wein1") (pin "6") (pinfunction "6_6") (pintype "passive"))
      (node (ref "Series wein1") (pin "8") (pinfunction "8_8") (pintype "passive"))
      (node (ref "U4") (pin "3") (pinfunction "IN1+_3") (pintype "input"))
    )
    (net (code "47") (name "Net-(U4B-IN2-)") (class "Default")
      (node (ref "H5") (pin "1") (pinfunction "1_1") (pintype "passive"))
      (node (ref "R11") (pin "2") (pinfunction "2_2") (pintype "passive"))
      (node (ref "U4") (pin "6") (pinfunction "IN2-_6") (pintype "input"))
    )
    (net (code "48") (name "Net-(U4B-OUT2)") (class "Default")
      (node (ref "H5") (pin "2") (pinfunction "2_2") (pintype "passive"))
      (node (ref "R13") (pin "1") (pinfunction "1_1") (pintype "passive"))
      (node (ref "U4") (pin "7") (pinfunction "OUT2_7") (pintype "output"))
    )
    (net (code "49") (name "unconnected-(IC3-NC-Pad8)") (class "Default")
      (node (ref "IC3") (pin "8") (pinfunction "NC_8") (pintype "passive"))
    )
    (net (code "50") (name "unconnected-(IC3-NONINVERTING_INPUT-Pad3)") (class "Default")
      (node (ref "IC3") (pin "3") (pinfunction "NONINVERTING_INPUT_3") (pintype "passive"))
    )
    (net (code "51") (name "unconnected-(IC3-OFFSET_NULL_2-Pad5)") (class "Default")
      (node (ref "IC3") (pin "5") (pinfunction "OFFSET_NULL_2_5") (pintype "passive"))
    )
    (net (code "52") (name "unconnected-(IC4-NC-Pad8)") (class "Default")
      (node (ref "IC4") (pin "8") (pinfunction "NC_8") (pintype "passive"))
    )
    (net (code "53") (name "unconnected-(IC4-OFFSET_NULL_1-Pad1)") (class "Default")
      (node (ref "IC4") (pin "1") (pinfunction "OFFSET_NULL_1_1") (pintype "passive"))
    )
    (net (code "54") (name "unconnected-(IC4-OFFSET_NULL_2-Pad5)") (class "Default")
      (node (ref "IC4") (pin "5") (pinfunction "OFFSET_NULL_2_5") (pintype "passive"))
    )
    (net (code "55") (name "unconnected-(IC5-NC-Pad8)") (class "Default")
      (node (ref "IC5") (pin "8") (pinfunction "NC_8") (pintype "passive"))
    )
    (net (code "56") (name "unconnected-(IC5-OFFSET_NULL_1-Pad1)") (class "Default")
      (node (ref "IC5") (pin "1") (pinfunction "OFFSET_NULL_1_1") (pintype "passive"))
    )
    (net (code "57") (name "unconnected-(IC5-OFFSET_NULL_2-Pad5)") (class "Default")
      (node (ref "IC5") (pin "5") (pinfunction "OFFSET_NULL_2_5") (pintype "passive"))
    )
  )
)
